# PhotoShieldV2.net
KiCad netlist of a schematic drawn in EAGLE
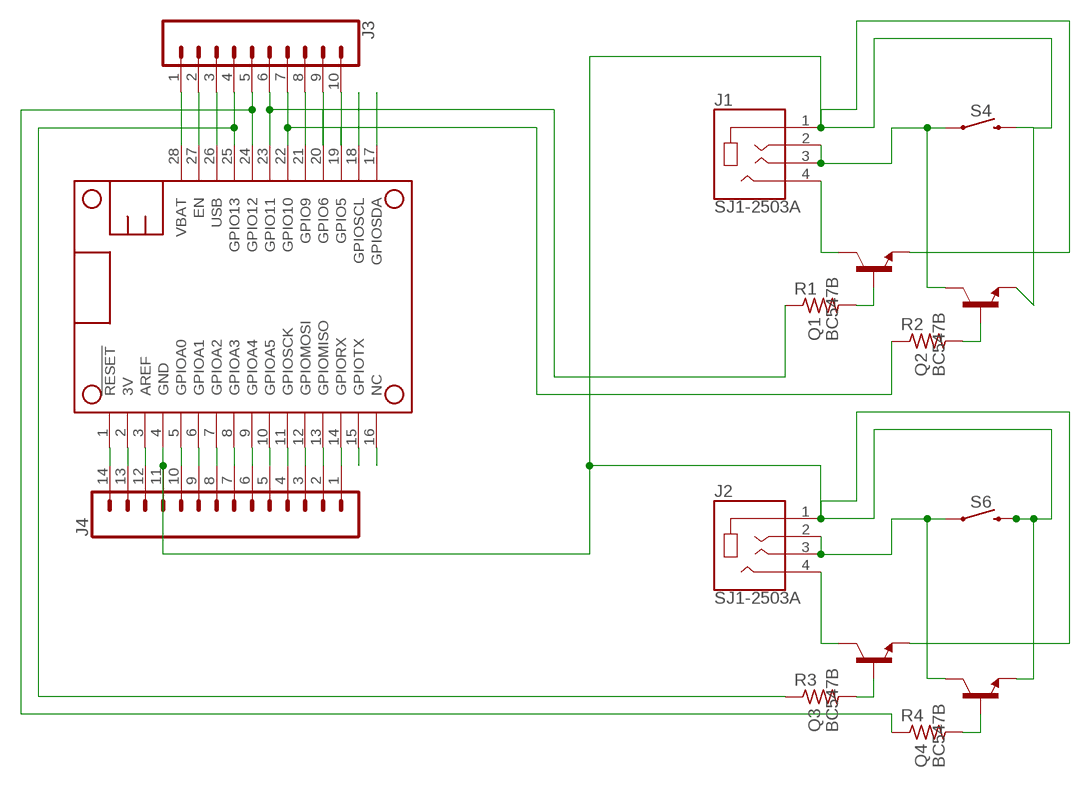
[diagram p0: schematic, sheet 1]

(export (version "E")
  (design (tool "Eeschema 10.0.6"))
  (components
    (comp (ref "J1")
      (value "SJ1-2503A")
      (footprint "eagle-import:CUI_SJ1-2503A")
      (fields (field (name "MANUFACTURER") "CUI INC"))
      (libsource (lib "eagle-import") (part "SJ1-2503A"))
    )
    (comp (ref "J2")
      (value "SJ1-2503A")
      (footprint "eagle-import:CUI_SJ1-2503A")
      (fields (field (name "MANUFACTURER") "CUI INC"))
      (libsource (lib "eagle-import") (part "SJ1-2503A"))
    )
    (comp (ref "J3")
      (value "CONN_10\"")
      (footprint "eagle-import:1X10")
      (libsource (lib "eagle-import") (part "CONN_10{dblquote}"))
    )
    (comp (ref "J4")
      (value "CONN_14")
      (footprint "eagle-import:1X14")
      (libsource (lib "eagle-import") (part "CONN_14"))
    )
    (comp (ref "MS1")
      (value "FEATHERWING")
      (footprint "eagle-import:FEATHERWING")
      (libsource (lib "eagle-import") (part "FEATHERWING"))
    )
    (comp (ref "Q1")
      (value "BC547B")
      (footprint "eagle-import:TO92")
      (libsource (lib "eagle-import") (part "BC547B"))
    )
    (comp (ref "Q2")
      (value "BC547B")
      (footprint "eagle-import:TO92")
      (libsource (lib "eagle-import") (part "BC547B"))
    )
    (comp (ref "Q3")
      (value "BC547B")
      (footprint "eagle-import:TO92")
      (libsource (lib "eagle-import") (part "BC547B"))
    )
    (comp (ref "Q4")
      (value "BC547B")
      (footprint "eagle-import:TO92")
      (libsource (lib "eagle-import") (part "BC547B"))
    )
    (comp (ref "R1")
      (value "R-US_R0805")
      (footprint "eagle-import:R0805")
      (libsource (lib "eagle-import") (part "R-US_R0805"))
    )
    (comp (ref "R2")
      (value "R-US_R0805")
      (footprint "eagle-import:R0805")
      (libsource (lib "eagle-import") (part "R-US_R0805"))
    )
    (comp (ref "R3")
      (value "R-US_R0805")
      (footprint "eagle-import:R0805")
      (libsource (lib "eagle-import") (part "R-US_R0805"))
    )
    (comp (ref "R4")
      (value "R-US_R0805")
      (footprint "eagle-import:R0805")
      (libsource (lib "eagle-import") (part "R-US_R0805"))
    )
    (comp (ref "S4")
      (value "MOMENTARY-SWITCH-SPST-SMD-4.6X2.8MM")
      (footprint "eagle-import:TACTILE_SWITCH_SMD_4.6X2.8MM")
      (libsource (lib "eagle-import") (part "MOMENTARY-SWITCH-SPST-SMD-4.6X2.8MM"))
    )
    (comp (ref "S6")
      (value "MOMENTARY-SWITCH-SPST-SMD-4.6X2.8MM")
      (footprint "eagle-import:TACTILE_SWITCH_SMD_4.6X2.8MM")
      (libsource (lib "eagle-import") (part "MOMENTARY-SWITCH-SPST-SMD-4.6X2.8MM"))
    )
  )
  (nets
    (net (code "1") (name "Net-(MS1-3V)") (class "Default")
      (node (ref "J4") (pin "13") (pinfunction "13_13") (pintype "passive"))
      (node (ref "MS1") (pin "2") (pinfunction "3V_2") (pintype "power_in"))
    )
    (net (code "2") (name "Net-(MS1-AREF)") (class "Default")
      (node (ref "J4") (pin "12") (pinfunction "12_12") (pintype "passive"))
      (node (ref "MS1") (pin "3") (pinfunction "AREF_3") (pintype "passive"))
    )
    (net (code "3") (name "Net-(MS1-EN)") (class "Default")
      (node (ref "J3") (pin "2") (pinfunction "2_2") (pintype "passive"))
      (node (ref "MS1") (pin "27") (pinfunction "EN_27") (pintype "passive"))
    )
    (net (code "4") (name "Net-(MS1-GND)") (class "Default")
      (node (ref "J1") (pin "1") (pinfunction "1_1") (pintype "passive"))
      (node (ref "J2") (pin "1") (pinfunction "1_1") (pintype "passive"))
      (node (ref "J4") (pin "11") (pinfunction "11_11") (pintype "passive"))
      (node (ref "MS1") (pin "4") (pinfunction "GND_4") (pintype "power_in"))
      (node (ref "Q1") (pin "1") (pinfunction "E_1") (pintype "passive"))
      (node (ref "Q2") (pin "1") (pinfunction "E_1") (pintype "passive"))
      (node (ref "Q3") (pin "1") (pinfunction "E_1") (pintype "passive"))
      (node (ref "Q4") (pin "1") (pinfunction "E_1") (pintype "passive"))
      (node (ref "S4") (pin "3") (pinfunction "2_3") (pintype "passive"))
      (node (ref "S4") (pin "4") (pinfunction "2_4") (pintype "passive"))
      (node (ref "S6") (pin "3") (pinfunction "2_3") (pintype "passive"))
      (node (ref "S6") (pin "4") (pinfunction "2_4") (pintype "passive"))
    )
    (net (code "5") (name "Net-(MS1-GPIO5)") (class "Default")
      (node (ref "J3") (pin "10") (pinfunction "10_10") (pintype "passive"))
      (node (ref "MS1") (pin "19") (pinfunction "GPIO5_19") (pintype "bidirectional"))
    )
    (net (code "6") (name "Net-(MS1-GPIO6)") (class "Default")
      (node (ref "J3") (pin "9") (pinfunction "9_9") (pintype "passive"))
      (node (ref "MS1") (pin "20") (pinfunction "GPIO6_20") (pintype "bidirectional"))
    )
    (net (code "7") (name "Net-(MS1-GPIO9)") (class "Default")
      (node (ref "J3") (pin "8") (pinfunction "8_8") (pintype "passive"))
      (node (ref "MS1") (pin "21") (pinfunction "GPIO9_21") (pintype "bidirectional"))
    )
    (net (code "8") (name "Net-(MS1-GPIO10)") (class "Default")
      (node (ref "J3") (pin "7") (pinfunction "7_7") (pintype "passive"))
      (node (ref "MS1") (pin "22") (pinfunction "GPIO10_22") (pintype "bidirectional"))
      (node (ref "R2") (pin "1") (pinfunction "1_1") (pintype "passive"))
    )
    (net (code "9") (name "Net-(MS1-GPIO11)") (class "Default")
      (node (ref "J3") (pin "6") (pinfunction "6_6") (pintype "passive"))
      (node (ref "MS1") (pin "23") (pinfunction "GPIO11_23") (pintype "bidirectional"))
      (node (ref "R1") (pin "1") (pinfunction "1_1") (pintype "passive"))
    )
    (net (code "10") (name "Net-(MS1-GPIO12)") (class "Default")
      (node (ref "J3") (pin "5") (pinfunction "5_5") (pintype "passive"))
      (node (ref "MS1") (pin "24") (pinfunction "GPIO12_24") (pintype "bidirectional"))
      (node (ref "R4") (pin "1") (pinfunction "1_1") (pintype "passive"))
    )
    (net (code "11") (name "Net-(MS1-GPIO13)") (class "Default")
      (node (ref "J3") (pin "4") (pinfunction "4_4") (pintype "passive"))
      (node (ref "MS1") (pin "25") (pinfunction "GPIO13_25") (pintype "bidirectional"))
      (node (ref "R3") (pin "1") (pinfunction "1_1") (pintype "passive"))
    )
    (net (code "12") (name "Net-(MS1-GPIOA0)") (class "Default")
      (node (ref "J4") (pin "10") (pinfunction "10_10") (pintype "passive"))
      (node (ref "MS1") (pin "5") (pinfunction "GPIOA0_5") (pintype "bidirectional"))
    )
    (net (code "13") (name "Net-(MS1-GPIOA1)") (class "Default")
      (node (ref "J4") (pin "9") (pinfunction "9_9") (pintype "passive"))
      (node (ref "MS1") (pin "6") (pinfunction "GPIOA1_6") (pintype "bidirectional"))
    )
    (net (code "14") (name "Net-(MS1-GPIOA2)") (class "Default")
      (node (ref "J4") (pin "8") (pinfunction "8_8") (pintype "passive"))
      (node (ref "MS1") (pin "7") (pinfunction "GPIOA2_7") (pintype "bidirectional"))
    )
    (net (code "15") (name "Net-(MS1-GPIOA3)") (class "Default")
      (node (ref "J4") (pin "7") (pinfunction "7_7") (pintype "passive"))
      (node (ref "MS1") (pin "8") (pinfunction "GPIOA3_8") (pintype "bidirectional"))
    )
    (net (code "16") (name "Net-(MS1-GPIOA4)") (class "Default")
      (node (ref "J4") (pin "6") (pinfunction "6_6") (pintype "passive"))
      (node (ref "MS1") (pin "9") (pinfunction "GPIOA4_9") (pintype "bidirectional"))
    )
    (net (code "17") (name "Net-(MS1-GPIOA5)") (class "Default")
      (node (ref "J4") (pin "5") (pinfunction "5_5") (pintype "passive"))
      (node (ref "MS1") (pin "10") (pinfunction "GPIOA5_10") (pintype "bidirectional"))
    )
    (net (code "18") (name "Net-(MS1-GPIOMISO)") (class "Default")
      (node (ref "J4") (pin "2") (pinfunction "2_2") (pintype "passive"))
      (node (ref "MS1") (pin "13") (pinfunction "GPIOMISO_13") (pintype "bidirectional"))
    )
    (net (code "19") (name "Net-(MS1-GPIOMOSI)") (class "Default")
      (node (ref "J4") (pin "3") (pinfunction "3_3") (pintype "passive"))
      (node (ref "MS1") (pin "12") (pinfunction "GPIOMOSI_12") (pintype "bidirectional"))
    )
    (net (code "20") (name "Net-(MS1-GPIORX)") (class "Default")
      (node (ref "J4") (pin "1") (pinfunction "1_1") (pintype "passive"))
      (node (ref "MS1") (pin "14") (pinfunction "GPIORX_14") (pintype "bidirectional"))
    )
    (net (code "21") (name "Net-(MS1-GPIOSCK)") (class "Default")
      (node (ref "J4") (pin "4") (pinfunction "4_4") (pintype "passive"))
      (node (ref "MS1") (pin "11") (pinfunction "GPIOSCK_11") (pintype "bidirectional"))
    )
    (net (code "22") (name "Net-(MS1-USB)") (class "Default")
      (node (ref "J3") (pin "3") (pinfunction "3_3") (pintype "passive"))
      (node (ref "MS1") (pin "26") (pinfunction "USB_26") (pintype "power_in"))
    )
    (net (code "23") (name "Net-(MS1-VBAT)") (class "Default")
      (node (ref "J3") (pin "1") (pinfunction "1_1") (pintype "passive"))
      (node (ref "MS1") (pin "28") (pinfunction "VBAT_28") (pintype "power_in"))
    )
    (net (code "24") (name "Net-(MS1-~{RESET})") (class "Default")
      (node (ref "J4") (pin "14") (pinfunction "14_14") (pintype "passive"))
      (node (ref "MS1") (pin "1") (pinfunction "~{RESET}_1") (pintype "input"))
    )
    (net (code "25") (name "Net-(Q1-B)") (class "Default")
      (node (ref "Q1") (pin "2") (pinfunction "B_2") (pintype "passive"))
      (node (ref "R1") (pin "2") (pinfunction "2_2") (pintype "passive"))
    )
    (net (code "26") (name "Net-(Q1-C)") (class "Default")
      (node (ref "J1") (pin "4") (pinfunction "4_4") (pintype "passive"))
      (node (ref "Q1") (pin "3") (pinfunction "C_3") (pintype "passive"))
    )
    (net (code "27") (name "Net-(Q2-B)") (class "Default")
      (node (ref "Q2") (pin "2") (pinfunction "B_2") (pintype "passive"))
      (node (ref "R2") (pin "2") (pinfunction "2_2") (pintype "passive"))
    )
    (net (code "28") (name "Net-(Q2-C)") (class "Default")
      (node (ref "J1") (pin "2") (pinfunction "2_2") (pintype "passive"))
      (node (ref "J1") (pin "3") (pinfunction "3_3") (pintype "passive"))
      (node (ref "Q2") (pin "3") (pinfunction "C_3") (pintype "passive"))
      (node (ref "S4") (pin "1") (pinfunction "1_1") (pintype "passive"))
      (node (ref "S4") (pin "2") (pinfunction "1_2") (pintype "passive"))
    )
    (net (code "29") (name "Net-(Q3-B)") (class "Default")
      (node (ref "Q3") (pin "2") (pinfunction "B_2") (pintype "passive"))
      (node (ref "R3") (pin "2") (pinfunction "2_2") (pintype "passive"))
    )
    (net (code "30") (name "Net-(Q3-C)") (class "Default")
      (node (ref "J2") (pin "4") (pinfunction "4_4") (pintype "passive"))
      (node (ref "Q3") (pin "3") (pinfunction "C_3") (pintype "passive"))
    )
    (net (code "31") (name "Net-(Q4-B)") (class "Default")
      (node (ref "Q4") (pin "2") (pinfunction "B_2") (pintype "passive"))
      (node (ref "R4") (pin "2") (pinfunction "2_2") (pintype "passive"))
    )
    (net (code "32") (name "Net-(Q4-C)") (class "Default")
      (node (ref "J2") (pin "2") (pinfunction "2_2") (pintype "passive"))
      (node (ref "J2") (pin "3") (pinfunction "3_3") (pintype "passive"))
      (node (ref "Q4") (pin "3") (pinfunction "C_3") (pintype "passive"))
      (node (ref "S6") (pin "1") (pinfunction "1_1") (pintype "passive"))
      (node (ref "S6") (pin "2") (pinfunction "1_2") (pintype "passive"))
    )
    (net (code "33") (name "unconnected-(MS1-GPIOSCL-Pad18)") (class "Default")
      (node (ref "MS1") (pin "18") (pinfunction "GPIOSCL_18") (pintype "bidirectional"))
    )
    (net (code "34") (name "unconnected-(MS1-GPIOSDA-Pad17)") (class "Default")
      (node (ref "MS1") (pin "17") (pinfunction "GPIOSDA_17") (pintype "bidirectional"))
    )
    (net (code "35") (name "unconnected-(MS1-GPIOTX-Pad15)") (class "Default")
      (node (ref "MS1") (pin "15") (pinfunction "GPIOTX_15") (pintype "bidirectional"))
    )
    (net (code "36") (name "unconnected-(MS1-NC-Pad16)") (class "Default")
      (node (ref "MS1") (pin "16") (pinfunction "NC_16") (pintype "passive"))
    )
  )
)
